# ScoutMakes_Hall_Sensor_v1.net
KiCad netlist of a schematic drawn in EAGLE
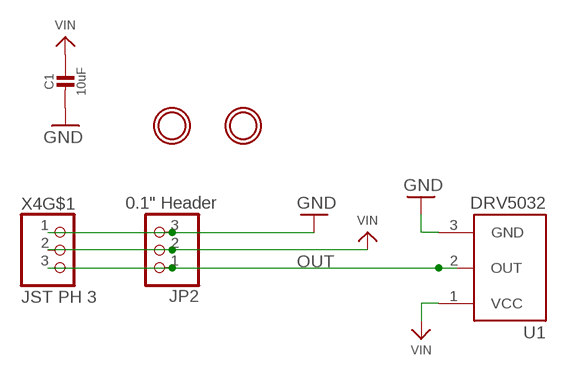
[diagram p0: schematic, sheet 1]

(export (version "E")
  (design (tool "Eeschema 10.0.6"))
  (components
    (comp (ref "C1")
      (value "10uF")
      (footprint "eagle-import:0805-NO")
      (libsource (lib "eagle-import") (part "CAP_CERAMIC0805-NOOUTLINE"))
    )
    (comp (ref "JP2")
      (value "0.1\" Header")
      (footprint "eagle-import:1X03_ROUND")
      (libsource (lib "eagle-import") (part "HEADER-1X3ROUND"))
    )
    (comp (ref "U$1")
      (value "MOUNTINGHOLE2.5")
      (footprint "eagle-import:MOUNTINGHOLE_2.5_PLATED")
      (libsource (lib "eagle-import") (part "MOUNTINGHOLE2.5"))
    )
    (comp (ref "U$8")
      (value "MOUNTINGHOLE2.5")
      (footprint "eagle-import:MOUNTINGHOLE_2.5_PLATED")
      (libsource (lib "eagle-import") (part "MOUNTINGHOLE2.5"))
    )
    (comp (ref "U1")
      (value "DRV5055A1QDBZT")
      (footprint "eagle-import:SOT95P237X112-3N")
      (fields
        (field (name "MF") "Texas Instruments")
        (field (name "MP") "DRV5055A1QDBZT")
        (field (name "MP_1") "DRV5032")
      )
      (libsource (lib "eagle-import") (part "DRV5055A1QDBZT"))
    )
    (comp (ref "X4")
      (value "JST PH 3")
      (footprint "eagle-import:JSTPH3")
      (libsource (lib "eagle-import") (part "CON_JST_PH_3PIN"))
    )
  )
  (nets
    (net (code "1") (name "/OUT") (class "Default")
      (node (ref "JP2") (pin "1") (pinfunction "1_1") (pintype "passive"))
      (node (ref "U1") (pin "2") (pinfunction "OUT_2") (pintype "output"))
      (node (ref "X4") (pin "3") (pinfunction "3_3") (pintype "passive"))
    )
    (net (code "2") (name "GND") (class "Default")
      (node (ref "C1") (pin "2") (pinfunction "2_2") (pintype "passive"))
      (node (ref "JP2") (pin "3") (pinfunction "3_3") (pintype "passive"))
      (node (ref "U1") (pin "3") (pinfunction "GND_3") (pintype "power_in"))
      (node (ref "X4") (pin "1") (pinfunction "1_1") (pintype "passive"))
    )
    (net (code "3") (name "VIN") (class "Default")
      (node (ref "C1") (pin "1") (pinfunction "1_1") (pintype "passive"))
      (node (ref "JP2") (pin "2") (pinfunction "2_2") (pintype "passive"))
      (node (ref "U1") (pin "1") (pinfunction "VCC_1") (pintype "power_in"))
      (node (ref "X4") (pin "2") (pinfunction "2_2") (pintype "passive"))
    )
  )
)
